# euroEnv.net
KiCad netlist of a schematic drawn in EAGLE
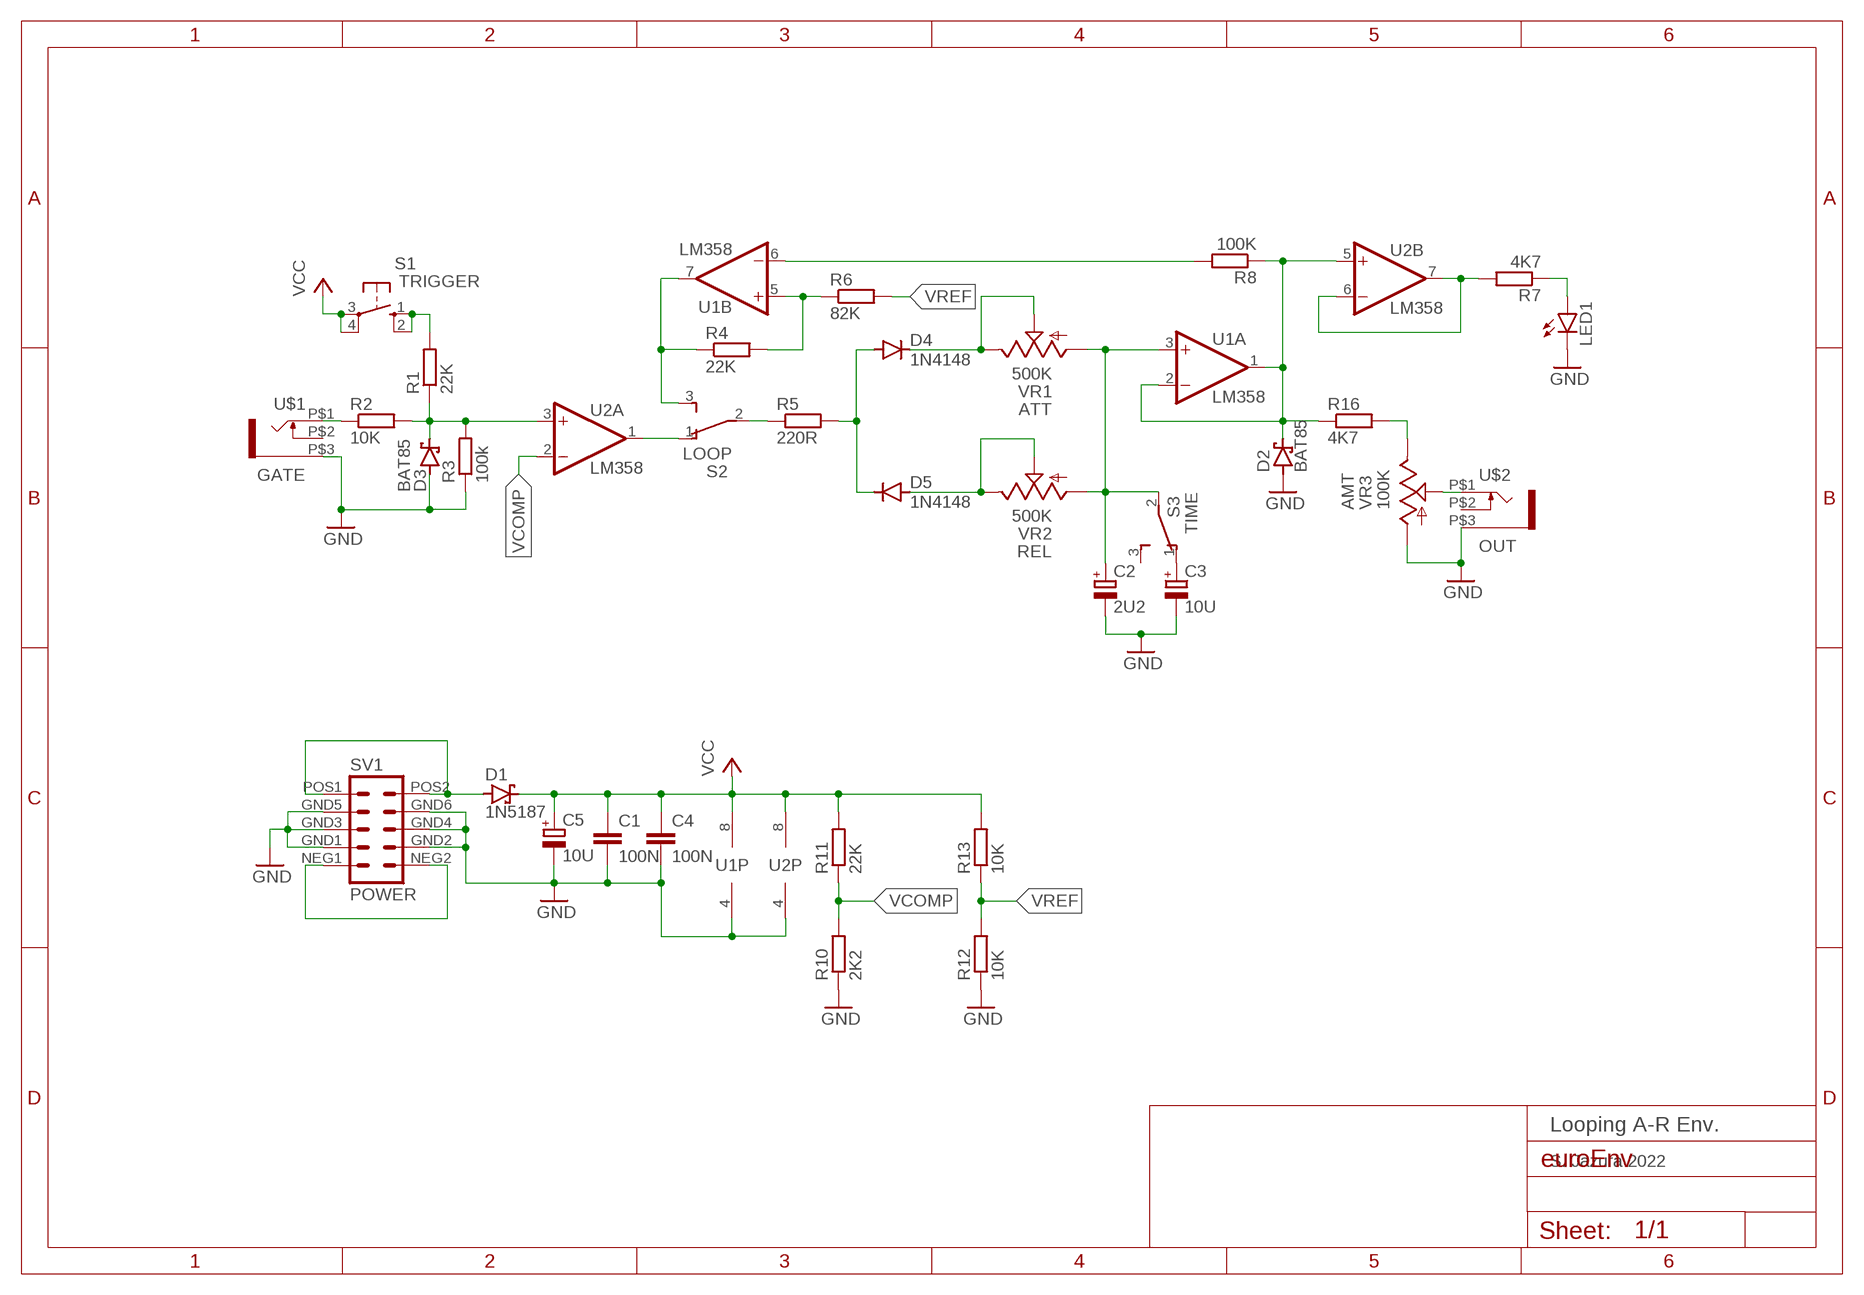
[diagram p0: schematic, sheet 1]

(export (version "E")
  (design (tool "Eeschema 10.0.6"))
  (components
    (comp (ref "C1")
      (value "100N")
      (footprint "eagle-import:000_7,5MM_FOIL_STANDARD")
      (libsource (lib "eagle-import") (part "0_C-EU000_7,5MM_FOIL_STANDARD"))
    )
    (comp (ref "C2")
      (value "2U2")
      (footprint "eagle-import:E2-5")
      (libsource (lib "eagle-import") (part "0_CPOL-EUE2-5"))
    )
    (comp (ref "C3")
      (value "10U")
      (footprint "eagle-import:E2-5")
      (libsource (lib "eagle-import") (part "0_CPOL-EUE2-5"))
    )
    (comp (ref "C4")
      (value "100N")
      (footprint "eagle-import:000_7,5MM_FOIL_STANDARD")
      (libsource (lib "eagle-import") (part "0_C-EU000_7,5MM_FOIL_STANDARD"))
    )
    (comp (ref "C5")
      (value "10U")
      (footprint "eagle-import:E2-5")
      (libsource (lib "eagle-import") (part "0_CPOL-EUE2-5"))
    )
    (comp (ref "D1")
      (value "1N5187")
      (footprint "eagle-import:000_MOD_7MM_BAT_4148")
      (libsource (lib "eagle-import") (part "SCHOTTKY-DIODEDO35-7"))
    )
    (comp (ref "D2")
      (value "BAT85")
      (footprint "eagle-import:000_MOD_7MM_BAT_4148")
      (libsource (lib "eagle-import") (part "BAT85DO35-7"))
    )
    (comp (ref "D3")
      (value "BAT85")
      (footprint "eagle-import:000_MOD_7MM_BAT_4148")
      (libsource (lib "eagle-import") (part "BAT85DO35-7"))
    )
    (comp (ref "D4")
      (value "1N4148")
      (footprint "eagle-import:000_MOD_7MM_BAT_4148")
      (libsource (lib "eagle-import") (part "1N4148DO35-7"))
    )
    (comp (ref "D5")
      (value "1N4148")
      (footprint "eagle-import:000_MOD_7MM_BAT_4148")
      (libsource (lib "eagle-import") (part "1N4148DO35-7"))
    )
    (comp (ref "LED1")
      (value "LED3MM")
      (footprint "eagle-import:LED3MM")
      (libsource (lib "eagle-import") (part "LED3MM"))
    )
    (comp (ref "R1")
      (value "22K")
      (footprint "eagle-import:000_7,5MM_STANDARD")
      (libsource (lib "eagle-import") (part "0_R-EU000_7,5MM_STANDARD"))
    )
    (comp (ref "R2")
      (value "10K")
      (footprint "eagle-import:000_7,5MM_STANDARD")
      (libsource (lib "eagle-import") (part "0_R-EU000_7,5MM_STANDARD"))
    )
    (comp (ref "R3")
      (value "100k")
      (footprint "eagle-import:000_7,5MM_STANDARD")
      (libsource (lib "eagle-import") (part "0_R-EU000_7,5MM_STANDARD"))
    )
    (comp (ref "R4")
      (value "22K")
      (footprint "eagle-import:000_7,5MM_STANDARD")
      (libsource (lib "eagle-import") (part "0_R-EU000_7,5MM_STANDARD"))
    )
    (comp (ref "R5")
      (value "220R")
      (footprint "eagle-import:000_7,5MM_STANDARD")
      (libsource (lib "eagle-import") (part "0_R-EU000_7,5MM_STANDARD"))
    )
    (comp (ref "R6")
      (value "82K")
      (footprint "eagle-import:000_7,5MM_STANDARD")
      (libsource (lib "eagle-import") (part "0_R-EU000_7,5MM_STANDARD"))
    )
    (comp (ref "R7")
      (value "4K7")
      (footprint "eagle-import:000_7,5MM_STANDARD")
      (libsource (lib "eagle-import") (part "0_R-EU000_7,5MM_STANDARD"))
    )
    (comp (ref "R8")
      (value "100K")
      (footprint "eagle-import:000_7,5MM_STANDARD")
      (libsource (lib "eagle-import") (part "0_R-EU000_7,5MM_STANDARD"))
    )
    (comp (ref "R10")
      (value "2K2")
      (footprint "eagle-import:000_7,5MM_STANDARD")
      (libsource (lib "eagle-import") (part "0_R-EU000_7,5MM_STANDARD"))
    )
    (comp (ref "R11")
      (value "22K")
      (footprint "eagle-import:000_7,5MM_STANDARD")
      (libsource (lib "eagle-import") (part "0_R-EU000_7,5MM_STANDARD"))
    )
    (comp (ref "R12")
      (value "10K")
      (footprint "eagle-import:000_7,5MM_STANDARD")
      (libsource (lib "eagle-import") (part "0_R-EU000_7,5MM_STANDARD"))
    )
    (comp (ref "R13")
      (value "10K")
      (footprint "eagle-import:000_7,5MM_STANDARD")
      (libsource (lib "eagle-import") (part "0_R-EU000_7,5MM_STANDARD"))
    )
    (comp (ref "R16")
      (value "4K7")
      (footprint "eagle-import:000_7,5MM_STANDARD")
      (libsource (lib "eagle-import") (part "0_R-EU000_7,5MM_STANDARD"))
    )
    (comp (ref "S1")
      (value "TRIGGER")
      (footprint "eagle-import:D3R_CK_SWITCH")
      (fields (field (name "MPN") "B3F-1000"))
      (libsource (lib "eagle-import") (part "D3R_CK_SWITCH"))
    )
    (comp (ref "S2")
      (value "LOOP")
      (footprint "eagle-import:M9040P")
      (libsource (lib "eagle-import") (part "SPDT_LUG_PCMOUNT"))
    )
    (comp (ref "S3")
      (value "TIME")
      (footprint "eagle-import:M9040P")
      (libsource (lib "eagle-import") (part "SPDT_LUG_PCMOUNT"))
    )
    (comp (ref "SV1")
      (value "POWER")
      (footprint "eagle-import:EURO_PWR_HEADER_LOCK")
      (libsource (lib "eagle-import") (part "EURO_POWER_HEADERLOCK_PADS"))
    )
    (comp (ref "U$1")
      (value "GATE")
      (footprint "eagle-import:WQP-PJ301M-12_JACK")
      (libsource (lib "eagle-import") (part "WQP-PJ301M-12_JACK"))
    )
    (comp (ref "U$2")
      (value "OUT")
      (footprint "eagle-import:WQP-PJ301M-12_JACK")
      (libsource (lib "eagle-import") (part "WQP-PJ301M-12_JACK"))
    )
    (comp (ref "U1")
      (value "LM358")
      (footprint "eagle-import:DIL08")
      (libsource (lib "eagle-import") (part "TL072_"))
    )
    (comp (ref "U2")
      (value "LM358")
      (footprint "eagle-import:DIL08")
      (libsource (lib "eagle-import") (part "TL072_"))
    )
    (comp (ref "VR1")
      (value "500K")
      (footprint "eagle-import:9MM_SNAP-IN_POT")
      (libsource (lib "eagle-import") (part "9MM_SNAP-IN_POT_"))
    )
    (comp (ref "VR2")
      (value "500K")
      (footprint "eagle-import:9MM_SNAP-IN_POT")
      (libsource (lib "eagle-import") (part "9MM_SNAP-IN_POT_"))
    )
    (comp (ref "VR3")
      (value "100K")
      (footprint "eagle-import:9MM_SNAP-IN_POT")
      (libsource (lib "eagle-import") (part "9MM_SNAP-IN_POT_"))
    )
  )
  (nets
    (net (code "1") (name "GND") (class "Default")
      (node (ref "C1") (pin "2") (pinfunction "2_2") (pintype "passive"))
      (node (ref "C2") (pin "-") (pinfunction "-_-") (pintype "passive"))
      (node (ref "C3") (pin "-") (pinfunction "-_-") (pintype "passive"))
      (node (ref "C4") (pin "2") (pinfunction "2_2") (pintype "passive"))
      (node (ref "C5") (pin "-") (pinfunction "-_-") (pintype "passive"))
      (node (ref "D2") (pin "A") (pinfunction "A_A") (pintype "passive"))
      (node (ref "D3") (pin "A") (pinfunction "A_A") (pintype "passive"))
      (node (ref "LED1") (pin "K") (pinfunction "C_K") (pintype "passive"))
      (node (ref "R10") (pin "1") (pinfunction "1_1") (pintype "passive"))
      (node (ref "R12") (pin "1") (pinfunction "1_1") (pintype "passive"))
      (node (ref "R3") (pin "1") (pinfunction "1_1") (pintype "passive"))
      (node (ref "SV1") (pin "GND1") (pinfunction "4_GND1") (pintype "passive"))
      (node (ref "SV1") (pin "GND2") (pinfunction "3_GND2") (pintype "passive"))
      (node (ref "SV1") (pin "GND3") (pinfunction "6_GND3") (pintype "passive"))
      (node (ref "SV1") (pin "GND4") (pinfunction "5_GND4") (pintype "passive"))
      (node (ref "SV1") (pin "GND5") (pinfunction "8_GND5") (pintype "passive"))
      (node (ref "SV1") (pin "GND6") (pinfunction "7_GND6") (pintype "passive"))
      (node (ref "U$1") (pin "P$3") (pinfunction "1_P$3") (pintype "passive"))
      (node (ref "U$2") (pin "P$3") (pinfunction "1_P$3") (pintype "passive"))
      (node (ref "U1") (pin "4") (pinfunction "V-_4") (pintype "power_in"))
      (node (ref "U2") (pin "4") (pinfunction "V-_4") (pintype "power_in"))
      (node (ref "VR3") (pin "1") (pinfunction "A_1") (pintype "passive"))
    )
    (net (code "2") (name "Net-(D4-PadA)") (class "Default")
      (node (ref "D4") (pin "A") (pinfunction "A_A") (pintype "passive"))
      (node (ref "D5") (pin "C") (pinfunction "C_C") (pintype "passive"))
      (node (ref "R5") (pin "2") (pinfunction "2_2") (pintype "passive"))
    )
    (net (code "3") (name "Net-(LED1-PadA)") (class "Default")
      (node (ref "LED1") (pin "A") (pinfunction "A_A") (pintype "passive"))
      (node (ref "R7") (pin "1") (pinfunction "1_1") (pintype "passive"))
    )
    (net (code "4") (name "Net-(S1-S)") (class "Default")
      (node (ref "R1") (pin "2") (pinfunction "2_2") (pintype "passive"))
      (node (ref "S1") (pin "1") (pinfunction "S_1") (pintype "passive"))
      (node (ref "S1") (pin "2") (pinfunction "S1_2") (pintype "passive"))
    )
    (net (code "5") (name "Net-(S2-O)") (class "Default")
      (node (ref "S2") (pin "1") (pinfunction "O_1") (pintype "passive"))
      (node (ref "U2") (pin "1") (pinfunction "OUT_1") (pintype "output"))
    )
    (net (code "6") (name "Net-(S2-P)") (class "Default")
      (node (ref "R5") (pin "1") (pinfunction "1_1") (pintype "passive"))
      (node (ref "S2") (pin "2") (pinfunction "P_2") (pintype "passive"))
    )
    (net (code "7") (name "Net-(S2-S)") (class "Default")
      (node (ref "R4") (pin "1") (pinfunction "1_1") (pintype "passive"))
      (node (ref "S2") (pin "3") (pinfunction "S_3") (pintype "passive"))
      (node (ref "U1") (pin "7") (pinfunction "OUT_7") (pintype "output"))
    )
    (net (code "8") (name "Net-(S3-O)") (class "Default")
      (node (ref "C3") (pin "+") (pinfunction "+_+") (pintype "passive"))
      (node (ref "S3") (pin "1") (pinfunction "O_1") (pintype "passive"))
    )
    (net (code "9") (name "Net-(S3-P)") (class "Default")
      (node (ref "C2") (pin "+") (pinfunction "+_+") (pintype "passive"))
      (node (ref "S3") (pin "2") (pinfunction "P_2") (pintype "passive"))
      (node (ref "U1") (pin "3") (pinfunction "+IN_3") (pintype "input"))
      (node (ref "VR1") (pin "1") (pinfunction "A_1") (pintype "passive"))
      (node (ref "VR2") (pin "1") (pinfunction "A_1") (pintype "passive"))
    )
    (net (code "10") (name "Net-(SV1-1)") (class "Default")
      (node (ref "SV1") (pin "NEG1") (pinfunction "2_NEG1") (pintype "passive"))
      (node (ref "SV1") (pin "NEG2") (pinfunction "1_NEG2") (pintype "passive"))
    )
    (net (code "11") (name "Net-(SV1-10)") (class "Default")
      (node (ref "D1") (pin "A") (pinfunction "A_A") (pintype "passive"))
      (node (ref "SV1") (pin "POS1") (pinfunction "10_POS1") (pintype "passive"))
      (node (ref "SV1") (pin "POS2") (pinfunction "9_POS2") (pintype "passive"))
    )
    (net (code "12") (name "Net-(U$1-2)") (class "Default")
      (node (ref "R2") (pin "1") (pinfunction "1_1") (pintype "passive"))
      (node (ref "U$1") (pin "P$1") (pinfunction "2_P$1") (pintype "passive"))
    )
    (net (code "13") (name "Net-(U$2-2)") (class "Default")
      (node (ref "U$2") (pin "P$1") (pinfunction "2_P$1") (pintype "passive"))
      (node (ref "VR3") (pin "2") (pinfunction "S_2") (pintype "passive"))
    )
    (net (code "14") (name "Net-(U1A--IN)") (class "Default")
      (node (ref "D2") (pin "C") (pinfunction "C_C") (pintype "passive"))
      (node (ref "R16") (pin "1") (pinfunction "1_1") (pintype "passive"))
      (node (ref "R8") (pin "1") (pinfunction "1_1") (pintype "passive"))
      (node (ref "U1") (pin "1") (pinfunction "OUT_1") (pintype "output"))
      (node (ref "U1") (pin "2") (pinfunction "-IN_2") (pintype "input"))
      (node (ref "U2") (pin "5") (pinfunction "+IN_5") (pintype "input"))
    )
    (net (code "15") (name "Net-(U1B-+IN)") (class "Default")
      (node (ref "R4") (pin "2") (pinfunction "2_2") (pintype "passive"))
      (node (ref "R6") (pin "1") (pinfunction "1_1") (pintype "passive"))
      (node (ref "U1") (pin "5") (pinfunction "+IN_5") (pintype "input"))
    )
    (net (code "16") (name "Net-(U1B--IN)") (class "Default")
      (node (ref "R8") (pin "2") (pinfunction "2_2") (pintype "passive"))
      (node (ref "U1") (pin "6") (pinfunction "-IN_6") (pintype "input"))
    )
    (net (code "17") (name "Net-(U2A-+IN)") (class "Default")
      (node (ref "D3") (pin "C") (pinfunction "C_C") (pintype "passive"))
      (node (ref "R1") (pin "1") (pinfunction "1_1") (pintype "passive"))
      (node (ref "R2") (pin "2") (pinfunction "2_2") (pintype "passive"))
      (node (ref "R3") (pin "2") (pinfunction "2_2") (pintype "passive"))
      (node (ref "U2") (pin "3") (pinfunction "+IN_3") (pintype "input"))
    )
    (net (code "18") (name "Net-(U2B--IN)") (class "Default")
      (node (ref "R7") (pin "2") (pinfunction "2_2") (pintype "passive"))
      (node (ref "U2") (pin "6") (pinfunction "-IN_6") (pintype "input"))
      (node (ref "U2") (pin "7") (pinfunction "OUT_7") (pintype "output"))
    )
    (net (code "19") (name "Net-(VR1-E)") (class "Default")
      (node (ref "D4") (pin "C") (pinfunction "C_C") (pintype "passive"))
      (node (ref "VR1") (pin "2") (pinfunction "S_2") (pintype "passive"))
      (node (ref "VR1") (pin "3") (pinfunction "E_3") (pintype "passive"))
    )
    (net (code "20") (name "Net-(VR2-E)") (class "Default")
      (node (ref "D5") (pin "A") (pinfunction "A_A") (pintype "passive"))
      (node (ref "VR2") (pin "2") (pinfunction "S_2") (pintype "passive"))
      (node (ref "VR2") (pin "3") (pinfunction "E_3") (pintype "passive"))
    )
    (net (code "21") (name "Net-(VR3-E)") (class "Default")
      (node (ref "R16") (pin "2") (pinfunction "2_2") (pintype "passive"))
      (node (ref "VR3") (pin "3") (pinfunction "E_3") (pintype "passive"))
    )
    (net (code "22") (name "VCC") (class "Default")
      (node (ref "C1") (pin "1") (pinfunction "1_1") (pintype "passive"))
      (node (ref "C4") (pin "1") (pinfunction "1_1") (pintype "passive"))
      (node (ref "C5") (pin "+") (pinfunction "+_+") (pintype "passive"))
      (node (ref "D1") (pin "C") (pinfunction "C_C") (pintype "passive"))
      (node (ref "R11") (pin "2") (pinfunction "2_2") (pintype "passive"))
      (node (ref "R13") (pin "2") (pinfunction "2_2") (pintype "passive"))
      (node (ref "S1") (pin "3") (pinfunction "P_3") (pintype "passive"))
      (node (ref "S1") (pin "4") (pinfunction "P1_4") (pintype "passive"))
      (node (ref "U1") (pin "8") (pinfunction "V+_8") (pintype "power_in"))
      (node (ref "U2") (pin "8") (pinfunction "V+_8") (pintype "power_in"))
    )
    (net (code "23") (name "VCOMP") (class "Default")
      (node (ref "R10") (pin "2") (pinfunction "2_2") (pintype "passive"))
      (node (ref "R11") (pin "1") (pinfunction "1_1") (pintype "passive"))
      (node (ref "U2") (pin "2") (pinfunction "-IN_2") (pintype "input"))
    )
    (net (code "24") (name "VREF") (class "Default")
      (node (ref "R12") (pin "2") (pinfunction "2_2") (pintype "passive"))
      (node (ref "R13") (pin "1") (pinfunction "1_1") (pintype "passive"))
      (node (ref "R6") (pin "2") (pinfunction "2_2") (pintype "passive"))
    )
    (net (code "25") (name "unconnected-(S3-S-Pad3)") (class "Default")
      (node (ref "S3") (pin "3") (pinfunction "S_3") (pintype "passive"))
    )
    (net (code "26") (name "unconnected-(U$1-3-PadP$2)") (class "Default")
      (node (ref "U$1") (pin "P$2") (pinfunction "3_P$2") (pintype "passive"))
    )
    (net (code "27") (name "unconnected-(U$2-3-PadP$2)") (class "Default")
      (node (ref "U$2") (pin "P$2") (pinfunction "3_P$2") (pintype "passive"))
    )
  )
)
